# Cpcis_connectors_P1_P6.net
KiCad netlist of a schematic drawn in Altium Designer
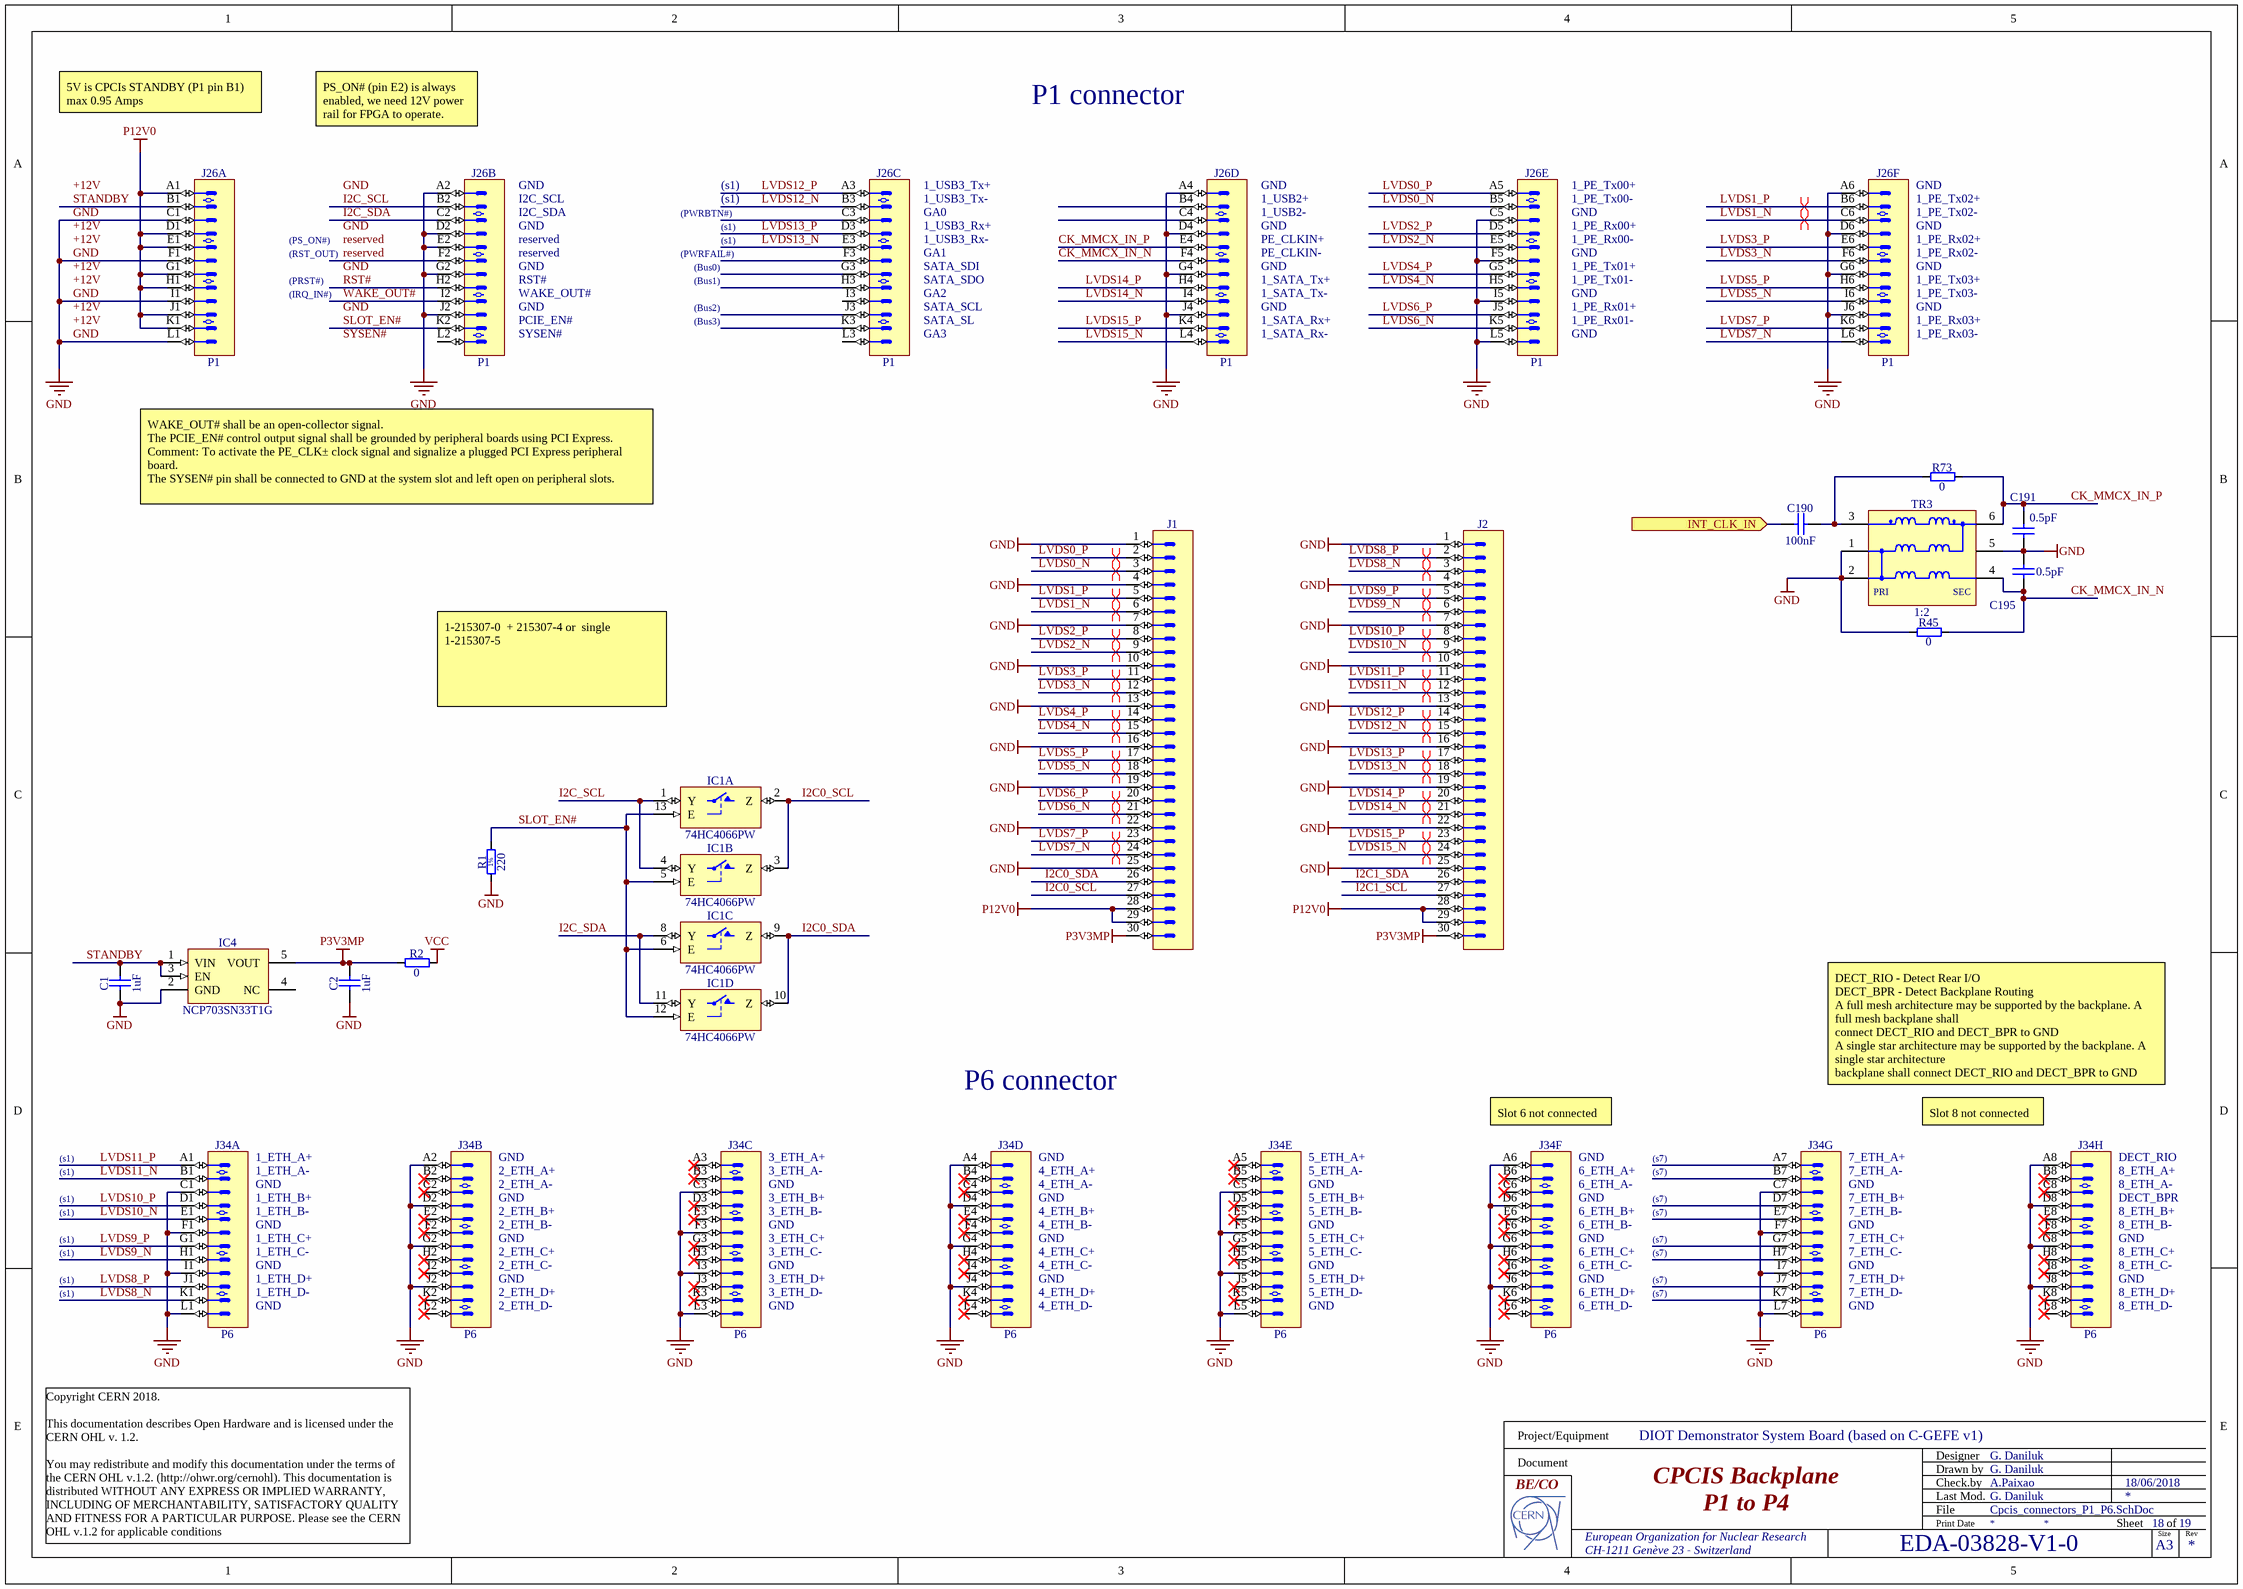
[diagram p0: Cpcis_connectors_P1_P6.SchDoc]

(export (version "E")
  (design (tool "Eeschema 10.0.6"))
  (components
    (comp (ref "C1")
      (value "1uF")
      (footprint "CAPC2012X140N")
      (description "Non-polarised capacitor")
      (fields
        (field (name "PART NUMBER") "CC0805_1UF_35V_20%_X7R")
        (field (name "VOLTAGE") "35V")
        (field (name "AUTHOR") "CERN DEM JLC")
      )
      (libsource (lib "Capacitors") (part "Capacitor - non polarized"))
    )
    (comp (ref "C2")
      (value "1uF")
      (footprint "CAPC2012X140N")
      (description "Non-polarised capacitor")
      (fields
        (field (name "PART NUMBER") "CC0805_1UF_35V_20%_X7R")
        (field (name "VOLTAGE") "35V")
        (field (name "AUTHOR") "CERN DEM JLC")
      )
      (libsource (lib "Capacitors") (part "Capacitor - non polarized"))
    )
    (comp (ref "C190")
      (value "100nF")
      (footprint "CAPC1005X55N")
      (description "Non-polarised capacitor")
      (fields
        (field (name "PART NUMBER") "CC0402_100NF_16V_10%_X5R")
        (field (name "VOLTAGE") "16V")
        (field (name "AUTHOR") "CERN DEM JLC")
      )
      (libsource (lib "Capacitors") (part "Capacitor - non polarized"))
    )
    (comp (ref "C191")
      (value "0.5pF")
      (footprint "CAPC1005X50N")
      (description "Non-polarised capacitor")
      (fields
        (field (name "PART NUMBER") "CC0402_0.5PF_25V_0.05PF_AVX_04023J0R5ABSTR")
        (field (name "VOLTAGE") "25V")
        (field (name "AUTHOR") "CERN DEM JLC")
      )
      (libsource (lib "Capacitors") (part "Capacitor - non polarized"))
    )
    (comp (ref "C195")
      (value "0.5pF")
      (footprint "CAPC1005X50N")
      (description "Non-polarised capacitor")
      (fields
        (field (name "PART NUMBER") "CC0402_0.5PF_25V_0.05PF_AVX_04023J0R5ABSTR")
        (field (name "VOLTAGE") "25V")
        (field (name "AUTHOR") "CERN DEM JLC")
      )
      (libsource (lib "Capacitors") (part "Capacitor - non polarized"))
    )
    (comp (ref "IC1")
      (value "74HC4066PW")
      (footprint "SOP65P640X110-14N")
      (fields (field (name "MANUFACTURER") "NXP SEMICONDUCTORS") (field (name "AUTHOR") "CERN DEM JLC"))
      (libsource (lib "ICs And Semiconductors") (part "4066"))
    )
    (comp (ref "IC4")
      (value "NCP703SN33T1G")
      (footprint "SOT95P275X110-5N")
      (description "3.3V 300mA, Ultra-Low Quiescent Current, IQ 12uA, Ultra-Low Noise, LDO Voltage Regulator")
      (fields (field (name "MANUFACTURER") "ON SEMICONDUCTOR") (field (name "AUTHOR") "CERN DEM JLC"))
      (libsource (lib "ICs And Semiconductors") (part "NCP703SN"))
    )
    (comp (ref "J1")
      (value "~")
      (footprint "3M_N2530-6002RB")
      (description "Connector 30 Male")
      (fields
        (field (name "PART NUMBER") "3M_N2530-6002RB")
        (field (name "MANUFACTURER") "3M")
        (field (name "AUTHOR") "CERN DEM JLC")
      )
      (libsource (lib "Connectors") (part "Connector 30 Male"))
    )
    (comp (ref "J2")
      (value "~")
      (footprint "3M_N2530-6002RB")
      (description "Connector 30 Male")
      (fields
        (field (name "PART NUMBER") "3M_N2530-6002RB")
        (field (name "MANUFACTURER") "3M")
        (field (name "AUTHOR") "CERN DEM JLC")
      )
      (libsource (lib "Connectors") (part "Connector 30 Male"))
    )
    (comp (ref "J26")
      (value "P1")
      (footprint "AMPHENOL_10052825-101LF")
      (description "72 Contacts Header, 6 Columns, 4 Pairs per Column")
      (fields
        (field (name "PART NUMBER") "AMPHENOL_10052825-101LF")
        (field (name "MANUFACTURER") "AMPHENOL")
        (field (name "AUTHOR") "CERN DEM MR")
      )
      (libsource (lib "Connectors") (part "AMPHENOL_10052825-101LF"))
    )
    (comp (ref "J34")
      (value "P6")
      (footprint "AMPHENOL_10052838-101LF")
      (description "96 Contacts Header, 8 Columns, 4 Pairs per Column")
      (fields
        (field (name "PART NUMBER") "AMPHENOL_10052838-101LF")
        (field (name "MANUFACTURER") "AMPHENOL")
        (field (name "AUTHOR") "CERN DEM MR")
      )
      (libsource (lib "Connectors") (part "AMPHENOL_10052838-101LF"))
    )
    (comp (ref "R1")
      (value "220")
      (footprint "RESC1608X55N")
      (description "Resistor - 1%")
      (fields
        (field (name "PART NUMBER") "R0603_220R_1%_0.1W_100PPM")
        (field (name "POWER") "0.1W")
        (field (name "AUTHOR") "CERN DEM JLC")
      )
      (libsource (lib "Resistors") (part "Resistor - 1%"))
    )
    (comp (ref "R2")
      (value "0")
      (footprint "RESC1005X40N")
      (description "Resistor")
      (fields
        (field (name "PART NUMBER") "R0402_0R_JUMPER")
        (field (name "MANUFACTURER") "GENERIC")
        (field (name "AUTHOR") "CERN DEM JLC")
      )
      (libsource (lib "Resistors") (part "Resistor"))
    )
    (comp (ref "R45")
      (value "0")
      (footprint "RESC1005X40N")
      (description "Resistor")
      (fields
        (field (name "PART NUMBER") "R0402_0R_JUMPER")
        (field (name "MANUFACTURER") "GENERIC")
        (field (name "AUTHOR") "CERN DEM JLC")
      )
      (libsource (lib "Resistors") (part "Resistor"))
    )
    (comp (ref "R73")
      (value "0")
      (footprint "RESC1005X40N")
      (description "Resistor")
      (fields
        (field (name "PART NUMBER") "R0402_0R_JUMPER")
        (field (name "MANUFACTURER") "GENERIC")
        (field (name "AUTHOR") "CERN DEM JLC")
      )
      (libsource (lib "Resistors") (part "Resistor"))
    )
    (comp (ref "TR3")
      (value "1:2")
      (footprint "XFMR_MINI-CIRCUITS_DB1627")
      (description "50 OHMS 10 to 4000 MHz RF Transformer")
      (fields
        (field (name "PART NUMBER") "XFMR_MINI-CIRCUITS_TCM2-43X+")
        (field (name "POWER") "0.4W")
        (field (name "AUTHOR") "CERN DEM BC")
      )
      (libsource (lib "Inductors & Transformers") (part "XFMR_MINI-CIRCUITS_TCM2-43X"))
    )
  )
  (nets
    (net (code "2") (name "/CK_MMCX_IN_N") (class "Default")
      (node (ref "C195") (pin "1") (pinfunction "1_1") (pintype "passive"))
      (node (ref "J26") (pin "F4") (pinfunction "F4_F4") (pintype "bidirectional"))
      (node (ref "R45") (pin "2") (pinfunction "2_2") (pintype "passive"))
      (node (ref "TR3") (pin "4") (pinfunction "S1_4") (pintype "passive"))
    )
    (net (code "3") (name "/CK_MMCX_IN_P") (class "Default")
      (node (ref "C191") (pin "2") (pinfunction "2_2") (pintype "passive"))
      (node (ref "J26") (pin "E4") (pinfunction "E4_E4") (pintype "bidirectional"))
      (node (ref "R73") (pin "2") (pinfunction "2_2") (pintype "passive"))
      (node (ref "TR3") (pin "6") (pinfunction "S1_6") (pintype "passive"))
    )
    (net (code "4") (name "/I2C0_SCL") (class "Default")
      (node (ref "IC1") (pin "2") (pinfunction "Z_2") (pintype "bidirectional"))
      (node (ref "IC1") (pin "3") (pinfunction "Z_3") (pintype "bidirectional"))
      (node (ref "J1") (pin "27") (pinfunction "27_27") (pintype "bidirectional"))
    )
    (net (code "5") (name "/I2C0_SDA") (class "Default")
      (node (ref "IC1") (pin "10") (pinfunction "Z_10") (pintype "bidirectional"))
      (node (ref "IC1") (pin "9") (pinfunction "Z_9") (pintype "bidirectional"))
      (node (ref "J1") (pin "26") (pinfunction "26_26") (pintype "bidirectional"))
    )
    (net (code "6") (name "/I2C1_SCL") (class "Default")
      (node (ref "J2") (pin "27") (pinfunction "27_27") (pintype "bidirectional"))
    )
    (net (code "7") (name "/I2C1_SDA") (class "Default")
      (node (ref "J2") (pin "26") (pinfunction "26_26") (pintype "bidirectional"))
    )
    (net (code "8") (name "/I2C_SCL") (class "Default")
      (node (ref "IC1") (pin "1") (pinfunction "Y_1") (pintype "bidirectional"))
      (node (ref "IC1") (pin "4") (pinfunction "Y_4") (pintype "bidirectional"))
      (node (ref "J26") (pin "B2") (pinfunction "B2_B2") (pintype "bidirectional"))
    )
    (net (code "9") (name "/I2C_SDA") (class "Default")
      (node (ref "IC1") (pin "11") (pinfunction "Y_11") (pintype "bidirectional"))
      (node (ref "IC1") (pin "8") (pinfunction "Y_8") (pintype "bidirectional"))
      (node (ref "J26") (pin "C2") (pinfunction "C2_C2") (pintype "bidirectional"))
    )
    (net (code "10") (name "/INT_CLK_IN") (class "Default")
      (node (ref "C190") (pin "1") (pinfunction "1_1") (pintype "passive"))
    )
    (net (code "11") (name "/LVDS0_N") (class "Default")
      (node (ref "J1") (pin "3") (pinfunction "3_3") (pintype "bidirectional"))
      (node (ref "J26") (pin "B5") (pinfunction "B5_B5") (pintype "bidirectional"))
    )
    (net (code "12") (name "/LVDS0_P") (class "Default")
      (node (ref "J1") (pin "2") (pinfunction "2_2") (pintype "bidirectional"))
      (node (ref "J26") (pin "A5") (pinfunction "A5_A5") (pintype "bidirectional"))
    )
    (net (code "13") (name "/LVDS1_N") (class "Default")
      (node (ref "J1") (pin "6") (pinfunction "6_6") (pintype "bidirectional"))
      (node (ref "J26") (pin "C6") (pinfunction "C6_C6") (pintype "bidirectional"))
    )
    (net (code "14") (name "/LVDS1_P") (class "Default")
      (node (ref "J1") (pin "5") (pinfunction "5_5") (pintype "bidirectional"))
      (node (ref "J26") (pin "B6") (pinfunction "B6_B6") (pintype "bidirectional"))
    )
    (net (code "15") (name "/LVDS2_N") (class "Default")
      (node (ref "J1") (pin "9") (pinfunction "9_9") (pintype "bidirectional"))
      (node (ref "J26") (pin "E5") (pinfunction "E5_E5") (pintype "bidirectional"))
    )
    (net (code "16") (name "/LVDS2_P") (class "Default")
      (node (ref "J1") (pin "8") (pinfunction "8_8") (pintype "bidirectional"))
      (node (ref "J26") (pin "D5") (pinfunction "D5_D5") (pintype "bidirectional"))
    )
    (net (code "17") (name "/LVDS3_N") (class "Default")
      (node (ref "J1") (pin "12") (pinfunction "12_12") (pintype "bidirectional"))
      (node (ref "J26") (pin "F6") (pinfunction "F6_F6") (pintype "bidirectional"))
    )
    (net (code "18") (name "/LVDS3_P") (class "Default")
      (node (ref "J1") (pin "11") (pinfunction "11_11") (pintype "bidirectional"))
      (node (ref "J26") (pin "E6") (pinfunction "E6_E6") (pintype "bidirectional"))
    )
    (net (code "19") (name "/LVDS4_N") (class "Default")
      (node (ref "J1") (pin "15") (pinfunction "15_15") (pintype "bidirectional"))
      (node (ref "J26") (pin "H5") (pinfunction "H5_H5") (pintype "bidirectional"))
    )
    (net (code "20") (name "/LVDS4_P") (class "Default")
      (node (ref "J1") (pin "14") (pinfunction "14_14") (pintype "bidirectional"))
      (node (ref "J26") (pin "G5") (pinfunction "G5_G5") (pintype "bidirectional"))
    )
    (net (code "21") (name "/LVDS5_N") (class "Default")
      (node (ref "J1") (pin "18") (pinfunction "18_18") (pintype "bidirectional"))
      (node (ref "J26") (pin "I6") (pinfunction "I6_I6") (pintype "bidirectional"))
    )
    (net (code "22") (name "/LVDS5_P") (class "Default")
      (node (ref "J1") (pin "17") (pinfunction "17_17") (pintype "bidirectional"))
      (node (ref "J26") (pin "H6") (pinfunction "H6_H6") (pintype "bidirectional"))
    )
    (net (code "23") (name "/LVDS6_N") (class "Default")
      (node (ref "J1") (pin "21") (pinfunction "21_21") (pintype "bidirectional"))
      (node (ref "J26") (pin "K5") (pinfunction "K5_K5") (pintype "bidirectional"))
    )
    (net (code "24") (name "/LVDS6_P") (class "Default")
      (node (ref "J1") (pin "20") (pinfunction "20_20") (pintype "bidirectional"))
      (node (ref "J26") (pin "J5") (pinfunction "J5_J5") (pintype "bidirectional"))
    )
    (net (code "25") (name "/LVDS7_N") (class "Default")
      (node (ref "J1") (pin "24") (pinfunction "24_24") (pintype "bidirectional"))
      (node (ref "J26") (pin "L6") (pinfunction "L6_L6") (pintype "bidirectional"))
    )
    (net (code "26") (name "/LVDS7_P") (class "Default")
      (node (ref "J1") (pin "23") (pinfunction "23_23") (pintype "bidirectional"))
      (node (ref "J26") (pin "K6") (pinfunction "K6_K6") (pintype "bidirectional"))
    )
    (net (code "27") (name "/LVDS8_N") (class "Default")
      (node (ref "J2") (pin "3") (pinfunction "3_3") (pintype "bidirectional"))
      (node (ref "J34") (pin "K1") (pinfunction "K1_K1") (pintype "bidirectional"))
    )
    (net (code "28") (name "/LVDS8_P") (class "Default")
      (node (ref "J2") (pin "2") (pinfunction "2_2") (pintype "bidirectional"))
      (node (ref "J34") (pin "J1") (pinfunction "J1_J1") (pintype "bidirectional"))
    )
    (net (code "29") (name "/LVDS9_N") (class "Default")
      (node (ref "J2") (pin "6") (pinfunction "6_6") (pintype "bidirectional"))
      (node (ref "J34") (pin "H1") (pinfunction "H1_H1") (pintype "bidirectional"))
    )
    (net (code "30") (name "/LVDS9_P") (class "Default")
      (node (ref "J2") (pin "5") (pinfunction "5_5") (pintype "bidirectional"))
      (node (ref "J34") (pin "G1") (pinfunction "G1_G1") (pintype "bidirectional"))
    )
    (net (code "31") (name "/LVDS10_N") (class "Default")
      (node (ref "J2") (pin "9") (pinfunction "9_9") (pintype "bidirectional"))
      (node (ref "J34") (pin "E1") (pinfunction "E1_E1") (pintype "bidirectional"))
    )
    (net (code "32") (name "/LVDS10_P") (class "Default")
      (node (ref "J2") (pin "8") (pinfunction "8_8") (pintype "bidirectional"))
      (node (ref "J34") (pin "D1") (pinfunction "D1_D1") (pintype "bidirectional"))
    )
    (net (code "33") (name "/LVDS11_N") (class "Default")
      (node (ref "J2") (pin "12") (pinfunction "12_12") (pintype "bidirectional"))
      (node (ref "J34") (pin "B1") (pinfunction "B1_B1") (pintype "bidirectional"))
    )
    (net (code "34") (name "/LVDS11_P") (class "Default")
      (node (ref "J2") (pin "11") (pinfunction "11_11") (pintype "bidirectional"))
      (node (ref "J34") (pin "A1") (pinfunction "A1_A1") (pintype "bidirectional"))
    )
    (net (code "35") (name "/LVDS12_N") (class "Default")
      (node (ref "J2") (pin "15") (pinfunction "15_15") (pintype "bidirectional"))
      (node (ref "J26") (pin "B3") (pinfunction "B3_B3") (pintype "bidirectional"))
    )
    (net (code "36") (name "/LVDS12_P") (class "Default")
      (node (ref "J2") (pin "14") (pinfunction "14_14") (pintype "bidirectional"))
      (node (ref "J26") (pin "A3") (pinfunction "A3_A3") (pintype "bidirectional"))
    )
    (net (code "37") (name "/LVDS13_N") (class "Default")
      (node (ref "J2") (pin "18") (pinfunction "18_18") (pintype "bidirectional"))
      (node (ref "J26") (pin "E3") (pinfunction "E3_E3") (pintype "bidirectional"))
    )
    (net (code "38") (name "/LVDS13_P") (class "Default")
      (node (ref "J2") (pin "17") (pinfunction "17_17") (pintype "bidirectional"))
      (node (ref "J26") (pin "D3") (pinfunction "D3_D3") (pintype "bidirectional"))
    )
    (net (code "39") (name "/LVDS14_N") (class "Default")
      (node (ref "J2") (pin "21") (pinfunction "21_21") (pintype "bidirectional"))
      (node (ref "J26") (pin "I4") (pinfunction "I4_I4") (pintype "bidirectional"))
    )
    (net (code "40") (name "/LVDS14_P") (class "Default")
      (node (ref "J2") (pin "20") (pinfunction "20_20") (pintype "bidirectional"))
      (node (ref "J26") (pin "H4") (pinfunction "H4_H4") (pintype "bidirectional"))
    )
    (net (code "41") (name "/LVDS15_N") (class "Default")
      (node (ref "J2") (pin "24") (pinfunction "24_24") (pintype "bidirectional"))
      (node (ref "J26") (pin "L4") (pinfunction "L4_L4") (pintype "bidirectional"))
    )
    (net (code "42") (name "/LVDS15_P") (class "Default")
      (node (ref "J2") (pin "23") (pinfunction "23_23") (pintype "bidirectional"))
      (node (ref "J26") (pin "K4") (pinfunction "K4_K4") (pintype "bidirectional"))
    )
    (net (code "43") (name "/RST#") (class "Default")
      (node (ref "J26") (pin "H2") (pinfunction "H2_H2") (pintype "bidirectional"))
    )
    (net (code "44") (name "/SLOT_EN#") (class "Default")
      (node (ref "IC1") (pin "12") (pinfunction "E_12") (pintype "input"))
      (node (ref "IC1") (pin "13") (pinfunction "E_13") (pintype "input"))
      (node (ref "IC1") (pin "5") (pinfunction "E_5") (pintype "input"))
      (node (ref "IC1") (pin "6") (pinfunction "E_6") (pintype "input"))
      (node (ref "J26") (pin "K2") (pinfunction "K2_K2") (pintype "bidirectional"))
      (node (ref "R1") (pin "2") (pinfunction "2_2") (pintype "passive"))
    )
    (net (code "45") (name "/STANDBY") (class "Default")
      (node (ref "C1") (pin "2") (pinfunction "2_2") (pintype "passive"))
      (node (ref "IC4") (pin "1") (pinfunction "VIN_1") (pintype "input"))
      (node (ref "IC4") (pin "3") (pinfunction "EN_3") (pintype "input"))
      (node (ref "J26") (pin "B1") (pinfunction "B1_B1") (pintype "bidirectional"))
    )
    (net (code "47") (name "/WAKE_OUT#") (class "Default")
      (node (ref "J26") (pin "I2") (pinfunction "I2_I2") (pintype "bidirectional"))
    )
    (net (code "48") (name "/reserved") (class "Default")
      (node (ref "J26") (pin "F2") (pinfunction "F2_F2") (pintype "bidirectional"))
    )
    (net (code "49") (name "GND") (class "Default")
      (node (ref "C1") (pin "1") (pinfunction "1_1") (pintype "passive"))
      (node (ref "C191") (pin "1") (pinfunction "1_1") (pintype "passive"))
      (node (ref "C195") (pin "2") (pinfunction "2_2") (pintype "passive"))
      (node (ref "C2") (pin "1") (pinfunction "1_1") (pintype "passive"))
      (node (ref "IC1") (pin "7") (pinfunction "GND_7") (pintype "power_in"))
      (node (ref "IC4") (pin "2") (pinfunction "GND_2") (pintype "power_in"))
      (node (ref "J1") (pin "1") (pinfunction "1_1") (pintype "bidirectional"))
      (node (ref "J1") (pin "10") (pinfunction "10_10") (pintype "bidirectional"))
      (node (ref "J1") (pin "13") (pinfunction "13_13") (pintype "bidirectional"))
      (node (ref "J1") (pin "16") (pinfunction "16_16") (pintype "bidirectional"))
      (node (ref "J1") (pin "19") (pinfunction "19_19") (pintype "bidirectional"))
      (node (ref "J1") (pin "22") (pinfunction "22_22") (pintype "bidirectional"))
      (node (ref "J1") (pin "25") (pinfunction "25_25") (pintype "bidirectional"))
      (node (ref "J1") (pin "4") (pinfunction "4_4") (pintype "bidirectional"))
      (node (ref "J1") (pin "7") (pinfunction "7_7") (pintype "bidirectional"))
      (node (ref "J2") (pin "1") (pinfunction "1_1") (pintype "bidirectional"))
      (node (ref "J2") (pin "10") (pinfunction "10_10") (pintype "bidirectional"))
      (node (ref "J2") (pin "13") (pinfunction "13_13") (pintype "bidirectional"))
      (node (ref "J2") (pin "16") (pinfunction "16_16") (pintype "bidirectional"))
      (node (ref "J2") (pin "19") (pinfunction "19_19") (pintype "bidirectional"))
      (node (ref "J2") (pin "22") (pinfunction "22_22") (pintype "bidirectional"))
      (node (ref "J2") (pin "25") (pinfunction "25_25") (pintype "bidirectional"))
      (node (ref "J2") (pin "4") (pinfunction "4_4") (pintype "bidirectional"))
      (node (ref "J2") (pin "7") (pinfunction "7_7") (pintype "bidirectional"))
      (node (ref "J26") (pin "A2") (pinfunction "A2_A2") (pintype "bidirectional"))
      (node (ref "J26") (pin "A4") (pinfunction "A4_A4") (pintype "bidirectional"))
      (node (ref "J26") (pin "A6") (pinfunction "A6_A6") (pintype "bidirectional"))
      (node (ref "J26") (pin "C1") (pinfunction "C1_C1") (pintype "bidirectional"))
      (node (ref "J26") (pin "C5") (pinfunction "C5_C5") (pintype "bidirectional"))
      (node (ref "J26") (pin "D2") (pinfunction "D2_D2") (pintype "bidirectional"))
      (node (ref "J26") (pin "D4") (pinfunction "D4_D4") (pintype "bidirectional"))
      (node (ref "J26") (pin "D6") (pinfunction "D6_D6") (pintype "bidirectional"))
      (node (ref "J26") (pin "E2") (pinfunction "E2_E2") (pintype "bidirectional"))
      (node (ref "J26") (pin "F1") (pinfunction "F1_F1") (pintype "bidirectional"))
      (node (ref "J26") (pin "F5") (pinfunction "F5_F5") (pintype "bidirectional"))
      (node (ref "J26") (pin "G2") (pinfunction "G2_G2") (pintype "bidirectional"))
      (node (ref "J26") (pin "G4") (pinfunction "G4_G4") (pintype "bidirectional"))
      (node (ref "J26") (pin "G6") (pinfunction "G6_G6") (pintype "bidirectional"))
      (node (ref "J26") (pin "I1") (pinfunction "I1_I1") (pintype "bidirectional"))
      (node (ref "J26") (pin "I5") (pinfunction "I5_I5") (pintype "bidirectional"))
      (node (ref "J26") (pin "J2") (pinfunction "J2_J2") (pintype "bidirectional"))
      (node (ref "J26") (pin "J4") (pinfunction "J4_J4") (pintype "bidirectional"))
      (node (ref "J26") (pin "J6") (pinfunction "J6_J6") (pintype "bidirectional"))
      (node (ref "J26") (pin "L1") (pinfunction "L1_L1") (pintype "bidirectional"))
      (node (ref "J26") (pin "L5") (pinfunction "L5_L5") (pintype "bidirectional"))
      (node (ref "J34") (pin "A2") (pinfunction "A2_A2") (pintype "bidirectional"))
      (node (ref "J34") (pin "A4") (pinfunction "A4_A4") (pintype "bidirectional"))
      (node (ref "J34") (pin "A6") (pinfunction "A6_A6") (pintype "bidirectional"))
      (node (ref "J34") (pin "A8") (pinfunction "A8_A8") (pintype "bidirectional"))
      (node (ref "J34") (pin "C1") (pinfunction "C1_C1") (pintype "bidirectional"))
      (node (ref "J34") (pin "C3") (pinfunction "C3_C3") (pintype "bidirectional"))
      (node (ref "J34") (pin "C5") (pinfunction "C5_C5") (pintype "bidirectional"))
      (node (ref "J34") (pin "C7") (pinfunction "C7_C7") (pintype "bidirectional"))
      (node (ref "J34") (pin "D2") (pinfunction "D2_D2") (pintype "bidirectional"))
      (node (ref "J34") (pin "D4") (pinfunction "D4_D4") (pintype "bidirectional"))
      (node (ref "J34") (pin "D6") (pinfunction "D6_D6") (pintype "bidirectional"))
      (node (ref "J34") (pin "D8") (pinfunction "D8_D8") (pintype "bidirectional"))
      (node (ref "J34") (pin "F1") (pinfunction "F1_F1") (pintype "bidirectional"))
      (node (ref "J34") (pin "F3") (pinfunction "F3_F3") (pintype "bidirectional"))
      (node (ref "J34") (pin "F5") (pinfunction "F5_F5") (pintype "bidirectional"))
      (node (ref "J34") (pin "F7") (pinfunction "F7_F7") (pintype "bidirectional"))
      (node (ref "J34") (pin "G2") (pinfunction "G2_G2") (pintype "bidirectional"))
      (node (ref "J34") (pin "G4") (pinfunction "G4_G4") (pintype "bidirectional"))
      (node (ref "J34") (pin "G6") (pinfunction "G6_G6") (pintype "bidirectional"))
      (node (ref "J34") (pin "G8") (pinfunction "G8_G8") (pintype "bidirectional"))
      (node (ref "J34") (pin "I1") (pinfunction "I1_I1") (pintype "bidirectional"))
      (node (ref "J34") (pin "I3") (pinfunction "I3_I3") (pintype "bidirectional"))
      (node (ref "J34") (pin "I5") (pinfunction "I5_I5") (pintype "bidirectional"))
      (node (ref "J34") (pin "I7") (pinfunction "I7_I7") (pintype "bidirectional"))
      (node (ref "J34") (pin "J2") (pinfunction "J2_J2") (pintype "bidirectional"))
      (node (ref "J34") (pin "J4") (pinfunction "J4_J4") (pintype "bidirectional"))
      (node (ref "J34") (pin "J6") (pinfunction "J6_J6") (pintype "bidirectional"))
      (node (ref "J34") (pin "J8") (pinfunction "J8_J8") (pintype "bidirectional"))
      (node (ref "J34") (pin "L1") (pinfunction "L1_L1") (pintype "bidirectional"))
      (node (ref "J34") (pin "L3") (pinfunction "L3_L3") (pintype "bidirectional"))
      (node (ref "J34") (pin "L5") (pinfunction "L5_L5") (pintype "bidirectional"))
      (node (ref "J34") (pin "L7") (pinfunction "L7_L7") (pintype "bidirectional"))
      (node (ref "R1") (pin "1") (pinfunction "1_1") (pintype "passive"))
      (node (ref "R45") (pin "1") (pinfunction "1_1") (pintype "passive"))
      (node (ref "TR3") (pin "1") (pinfunction "P1_1") (pintype "passive"))
      (node (ref "TR3") (pin "2") (pinfunction "P1_2") (pintype "passive"))
      (node (ref "TR3") (pin "5") (pinfunction "NC_5") (pintype "passive"))
    )
    (net (code "50") (name "Net-(C190-Pad2)") (class "Default")
      (node (ref "C190") (pin "2") (pinfunction "2_2") (pintype "passive"))
      (node (ref "R73") (pin "1") (pinfunction "1_1") (pintype "passive"))
      (node (ref "TR3") (pin "3") (pinfunction "P1_3") (pintype "passive"))
    )
    (net (code "51") (name "P3V3MP") (class "Default")
      (node (ref "C2") (pin "2") (pinfunction "2_2") (pintype "passive"))
      (node (ref "IC4") (pin "5") (pinfunction "VOUT_5") (pintype "power_in"))
      (node (ref "J1") (pin "30") (pinfunction "30_30") (pintype "bidirectional"))
      (node (ref "J2") (pin "30") (pinfunction "30_30") (pintype "bidirectional"))
      (node (ref "R2") (pin "1") (pinfunction "1_1") (pintype "passive"))
    )
    (net (code "52") (name "P12V0") (class "Default")
      (node (ref "J1") (pin "28") (pinfunction "28_28") (pintype "bidirectional"))
      (node (ref "J1") (pin "29") (pinfunction "29_29") (pintype "bidirectional"))
      (node (ref "J2") (pin "28") (pinfunction "28_28") (pintype "bidirectional"))
      (node (ref "J2") (pin "29") (pinfunction "29_29") (pintype "bidirectional"))
      (node (ref "J26") (pin "A1") (pinfunction "A1_A1") (pintype "bidirectional"))
      (node (ref "J26") (pin "D1") (pinfunction "D1_D1") (pintype "bidirectional"))
      (node (ref "J26") (pin "E1") (pinfunction "E1_E1") (pintype "bidirectional"))
      (node (ref "J26") (pin "G1") (pinfunction "G1_G1") (pintype "bidirectional"))
      (node (ref "J26") (pin "H1") (pinfunction "H1_H1") (pintype "bidirectional"))
      (node (ref "J26") (pin "J1") (pinfunction "J1_J1") (pintype "bidirectional"))
      (node (ref "J26") (pin "K1") (pinfunction "K1_K1") (pintype "bidirectional"))
    )
    (net (code "53") (name "VCC") (class "Default")
      (node (ref "IC1") (pin "14") (pinfunction "VCC_14") (pintype "power_in"))
      (node (ref "R2") (pin "2") (pinfunction "2_2") (pintype "passive"))
    )
    (net (code "54") (name "unconnected-(IC4-NC-Pad4)") (class "Default")
      (node (ref "IC4") (pin "4") (pinfunction "NC_4") (pintype "passive"))
    )
    (net (code "55") (name "unconnected-(J26-PadB4)") (class "Default")
      (node (ref "J26") (pin "B4") (pinfunction "B4_B4") (pintype "bidirectional"))
    )
    (net (code "56") (name "unconnected-(J26-PadC3)") (class "Default")
      (node (ref "J26") (pin "C3") (pinfunction "C3_C3") (pintype "bidirectional"))
    )
    (net (code "57") (name "unconnected-(J26-PadC4)") (class "Default")
      (node (ref "J26") (pin "C4") (pinfunction "C4_C4") (pintype "bidirectional"))
    )
    (net (code "58") (name "unconnected-(J26-PadF3)") (class "Default")
      (node (ref "J26") (pin "F3") (pinfunction "F3_F3") (pintype "bidirectional"))
    )
    (net (code "59") (name "unconnected-(J26-PadG3)") (class "Default")
      (node (ref "J26") (pin "G3") (pinfunction "G3_G3") (pintype "bidirectional"))
    )
    (net (code "60") (name "unconnected-(J26-PadH3)") (class "Default")
      (node (ref "J26") (pin "H3") (pinfunction "H3_H3") (pintype "bidirectional"))
    )
    (net (code "61") (name "unconnected-(J26-PadI3)") (class "Default")
      (node (ref "J26") (pin "I3") (pinfunction "I3_I3") (pintype "bidirectional"))
    )
    (net (code "62") (name "unconnected-(J26-PadJ3)") (class "Default")
      (node (ref "J26") (pin "J3") (pinfunction "J3_J3") (pintype "bidirectional"))
    )
    (net (code "63") (name "unconnected-(J26-PadK3)") (class "Default")
      (node (ref "J26") (pin "K3") (pinfunction "K3_K3") (pintype "bidirectional"))
    )
    (net (code "64") (name "unconnected-(J26-PadL2)") (class "Default")
      (node (ref "J26") (pin "L2") (pinfunction "L2_L2") (pintype "bidirectional"))
    )
    (net (code "65") (name "unconnected-(J26-PadL3)") (class "Default")
      (node (ref "J26") (pin "L3") (pinfunction "L3_L3") (pintype "bidirectional"))
    )
    (net (code "66") (name "unconnected-(J34-PadA3)") (class "Default")
      (node (ref "J34") (pin "A3") (pinfunction "A3_A3") (pintype "bidirectional+no_connect"))
    )
    (net (code "67") (name "unconnected-(J34-PadA5)") (class "Default")
      (node (ref "J34") (pin "A5") (pinfunction "A5_A5") (pintype "bidirectional+no_connect"))
    )
    (net (code "68") (name "unconnected-(J34-PadA7)") (class "Default")
      (node (ref "J34") (pin "A7") (pinfunction "A7_A7") (pintype "bidirectional"))
    )
    (net (code "69") (name "unconnected-(J34-PadB2)") (class "Default")
      (node (ref "J34") (pin "B2") (pinfunction "B2_B2") (pintype "bidirectional+no_connect"))
    )
    (net (code "70") (name "unconnected-(J34-PadB3)") (class "Default")
      (node (ref "J34") (pin "B3") (pinfunction "B3_B3") (pintype "bidirectional+no_connect"))
    )
    (net (code "71") (name "unconnected-(J34-PadB4)") (class "Default")
      (node (ref "J34") (pin "B4") (pinfunction "B4_B4") (pintype "bidirectional+no_connect"))
    )
    (net (code "72") (name "unconnected-(J34-PadB5)") (class "Default")
      (node (ref "J34") (pin "B5") (pinfunction "B5_B5") (pintype "bidirectional+no_connect"))
    )
    (net (code "73") (name "unconnected-(J34-PadB6)") (class "Default")
      (node (ref "J34") (pin "B6") (pinfunction "B6_B6") (pintype "bidirectional+no_connect"))
    )
    (net (code "74") (name "unconnected-(J34-PadB7)") (class "Default")
      (node (ref "J34") (pin "B7") (pinfunction "B7_B7") (pintype "bidirectional"))
    )
    (net (code "75") (name "unconnected-(J34-PadB8)") (class "Default")
      (node (ref "J34") (pin "B8") (pinfunction "B8_B8") (pintype "bidirectional+no_connect"))
    )
    (net (code "76") (name "unconnected-(J34-PadC2)") (class "Default")
      (node (ref "J34") (pin "C2") (pinfunction "C2_C2") (pintype "bidirectional+no_connect"))
    )
    (net (code "77") (name "unconnected-(J34-PadC4)") (class "Default")
      (node (ref "J34") (pin "C4") (pinfunction "C4_C4") (pintype "bidirectional+no_connect"))
    )
    (net (code "78") (name "unconnected-(J34-PadC6)") (class "Default")
      (node (ref "J34") (pin "C6") (pinfunction "C6_C6") (pintype "bidirectional+no_connect"))
    )
    (net (code "79") (name "unconnected-(J34-PadC8)") (class "Default")
      (node (ref "J34") (pin "C8") (pinfunction "C8_C8") (pintype "bidirectional+no_connect"))
    )
    (net (code "80") (name "unconnected-(J34-PadD3)") (class "Default")
      (node (ref "J34") (pin "D3") (pinfunction "D3_D3") (pintype "bidirectional+no_connect"))
    )
    (net (code "81") (name "unconnected-(J34-PadD5)") (class "Default")
      (node (ref "J34") (pin "D5") (pinfunction "D5_D5") (pintype "bidirectional+no_connect"))
    )
    (net (code "82") (name "unconnected-(J34-PadD7)") (class "Default")
      (node (ref "J34") (pin "D7") (pinfunction "D7_D7") (pintype "bidirectional"))
    )
    (net (code "83") (name "unconnected-(J34-PadE2)") (class "Default")
      (node (ref "J34") (pin "E2") (pinfunction "E2_E2") (pintype "bidirectional+no_connect"))
    )
    (net (code "84") (name "unconnected-(J34-PadE3)") (class "Default")
      (node (ref "J34") (pin "E3") (pinfunction "E3_E3") (pintype "bidirectional+no_connect"))
    )
    (net (code "85") (name "unconnected-(J34-PadE4)") (class "Default")
      (node (ref "J34") (pin "E4") (pinfunction "E4_E4") (pintype "bidirectional+no_connect"))
    )
    (net (code "86") (name "unconnected-(J34-PadE5)") (class "Default")
      (node (ref "J34") (pin "E5") (pinfunction "E5_E5") (pintype "bidirectional+no_connect"))
    )
    (net (code "87") (name "unconnected-(J34-PadE6)") (class "Default")
      (node (ref "J34") (pin "E6") (pinfunction "E6_E6") (pintype "bidirectional+no_connect"))
    )
    (net (code "88") (name "unconnected-(J34-PadE7)") (class "Default")
      (node (ref "J34") (pin "E7") (pinfunction "E7_E7") (pintype "bidirectional"))
    )
    (net (code "89") (name "unconnected-(J34-PadE8)") (class "Default")
      (node (ref "J34") (pin "E8") (pinfunction "E8_E8") (pintype "bidirectional+no_connect"))
    )
    (net (code "90") (name "unconnected-(J34-PadF2)") (class "Default")
      (node (ref "J34") (pin "F2") (pinfunction "F2_F2") (pintype "bidirectional+no_connect"))
    )
    (net (code "91") (name "unconnected-(J34-PadF4)") (class "Default")
      (node (ref "J34") (pin "F4") (pinfunction "F4_F4") (pintype "bidirectional+no_connect"))
    )
    (net (code "92") (name "unconnected-(J34-PadF6)") (class "Default")
      (node (ref "J34") (pin "F6") (pinfunction "F6_F6") (pintype "bidirectional+no_connect"))
    )
    (net (code "93") (name "unconnected-(J34-PadF8)") (class "Default")
      (node (ref "J34") (pin "F8") (pinfunction "F8_F8") (pintype "bidirectional+no_connect"))
    )
    (net (code "94") (name "unconnected-(J34-PadG3)") (class "Default")
      (node (ref "J34") (pin "G3") (pinfunction "G3_G3") (pintype "bidirectional+no_connect"))
    )
    (net (code "95") (name "unconnected-(J34-PadG5)") (class "Default")
      (node (ref "J34") (pin "G5") (pinfunction "G5_G5") (pintype "bidirectional+no_connect"))
    )
    (net (code "96") (name "unconnected-(J34-PadG7)") (class "Default")
      (node (ref "J34") (pin "G7") (pinfunction "G7_G7") (pintype "bidirectional"))
    )
    (net (code "97") (name "unconnected-(J34-PadH2)") (class "Default")
      (node (ref "J34") (pin "H2") (pinfunction "H2_H2") (pintype "bidirectional+no_connect"))
    )
    (net (code "98") (name "unconnected-(J34-PadH3)") (class "Default")
      (node (ref "J34") (pin "H3") (pinfunction "H3_H3") (pintype "bidirectional+no_connect"))
    )
    (net (code "99") (name "unconnected-(J34-PadH4)") (class "Default")
      (node (ref "J34") (pin "H4") (pinfunction "H4_H4") (pintype "bidirectional+no_connect"))
    )
    (net (code "100") (name "unconnected-(J34-PadH5)") (class "Default")
      (node (ref "J34") (pin "H5") (pinfunction "H5_H5") (pintype "bidirectional+no_connect"))
    )
    (net (code "101") (name "unconnected-(J34-PadH6)") (class "Default")
      (node (ref "J34") (pin "H6") (pinfunction "H6_H6") (pintype "bidirectional+no_connect"))
    )
    (net (code "102") (name "unconnected-(J34-PadH7)") (class "Default")
      (node (ref "J34") (pin "H7") (pinfunction "H7_H7") (pintype "bidirectional"))
    )
    (net (code "103") (name "unconnected-(J34-PadH8)") (class "Default")
      (node (ref "J34") (pin "H8") (pinfunction "H8_H8") (pintype "bidirectional+no_connect"))
    )
    (net (code "104") (name "unconnected-(J34-PadI2)") (class "Default")
      (node (ref "J34") (pin "I2") (pinfunction "I2_I2") (pintype "bidirectional+no_connect"))
    )
    (net (code "105") (name "unconnected-(J34-PadI4)") (class "Default")
      (node (ref "J34") (pin "I4") (pinfunction "I4_I4") (pintype "bidirectional+no_connect"))
    )
    (net (code "106") (name "unconnected-(J34-PadI6)") (class "Default")
      (node (ref "J34") (pin "I6") (pinfunction "I6_I6") (pintype "bidirectional+no_connect"))
    )
    (net (code "107") (name "unconnected-(J34-PadI8)") (class "Default")
      (node (ref "J34") (pin "I8") (pinfunction "I8_I8") (pintype "bidirectional+no_connect"))
    )
    (net (code "108") (name "unconnected-(J34-PadJ3)") (class "Default")
      (node (ref "J34") (pin "J3") (pinfunction "J3_J3") (pintype "bidirectional+no_connect"))
    )
    (net (code "109") (name "unconnected-(J34-PadJ5)") (class "Default")
      (node (ref "J34") (pin "J5") (pinfunction "J5_J5") (pintype "bidirectional+no_connect"))
    )
    (net (code "110") (name "unconnected-(J34-PadJ7)") (class "Default")
      (node (ref "J34") (pin "J7") (pinfunction "J7_J7") (pintype "bidirectional"))
    )
    (net (code "111") (name "unconnected-(J34-PadK2)") (class "Default")
      (node (ref "J34") (pin "K2") (pinfunction "K2_K2") (pintype "bidirectional+no_connect"))
    )
    (net (code "112") (name "unconnected-(J34-PadK3)") (class "Default")
      (node (ref "J34") (pin "K3") (pinfunction "K3_K3") (pintype "bidirectional+no_connect"))
    )
    (net (code "113") (name "unconnected-(J34-PadK4)") (class "Default")
      (node (ref "J34") (pin "K4") (pinfunction "K4_K4") (pintype "bidirectional+no_connect"))
    )
    (net (code "114") (name "unconnected-(J34-PadK5)") (class "Default")
      (node (ref "J34") (pin "K5") (pinfunction "K5_K5") (pintype "bidirectional+no_connect"))
    )
    (net (code "115") (name "unconnected-(J34-PadK6)") (class "Default")
      (node (ref "J34") (pin "K6") (pinfunction "K6_K6") (pintype "bidirectional+no_connect"))
    )
    (net (code "116") (name "unconnected-(J34-PadK7)") (class "Default")
      (node (ref "J34") (pin "K7") (pinfunction "K7_K7") (pintype "bidirectional"))
    )
    (net (code "117") (name "unconnected-(J34-PadK8)") (class "Default")
      (node (ref "J34") (pin "K8") (pinfunction "K8_K8") (pintype "bidirectional+no_connect"))
    )
    (net (code "118") (name "unconnected-(J34-PadL2)") (class "Default")
      (node (ref "J34") (pin "L2") (pinfunction "L2_L2") (pintype "bidirectional+no_connect"))
    )
    (net (code "119") (name "unconnected-(J34-PadL4)") (class "Default")
      (node (ref "J34") (pin "L4") (pinfunction "L4_L4") (pintype "bidirectional+no_connect"))
    )
    (net (code "120") (name "unconnected-(J34-PadL6)") (class "Default")
      (node (ref "J34") (pin "L6") (pinfunction "L6_L6") (pintype "bidirectional+no_connect"))
    )
    (net (code "121") (name "unconnected-(J34-PadL8)") (class "Default")
      (node (ref "J34") (pin "L8") (pinfunction "L8_L8") (pintype "bidirectional+no_connect"))
    )
  )
)
